# PCB.net
KiCad netlist of a schematic drawn in Altium Designer
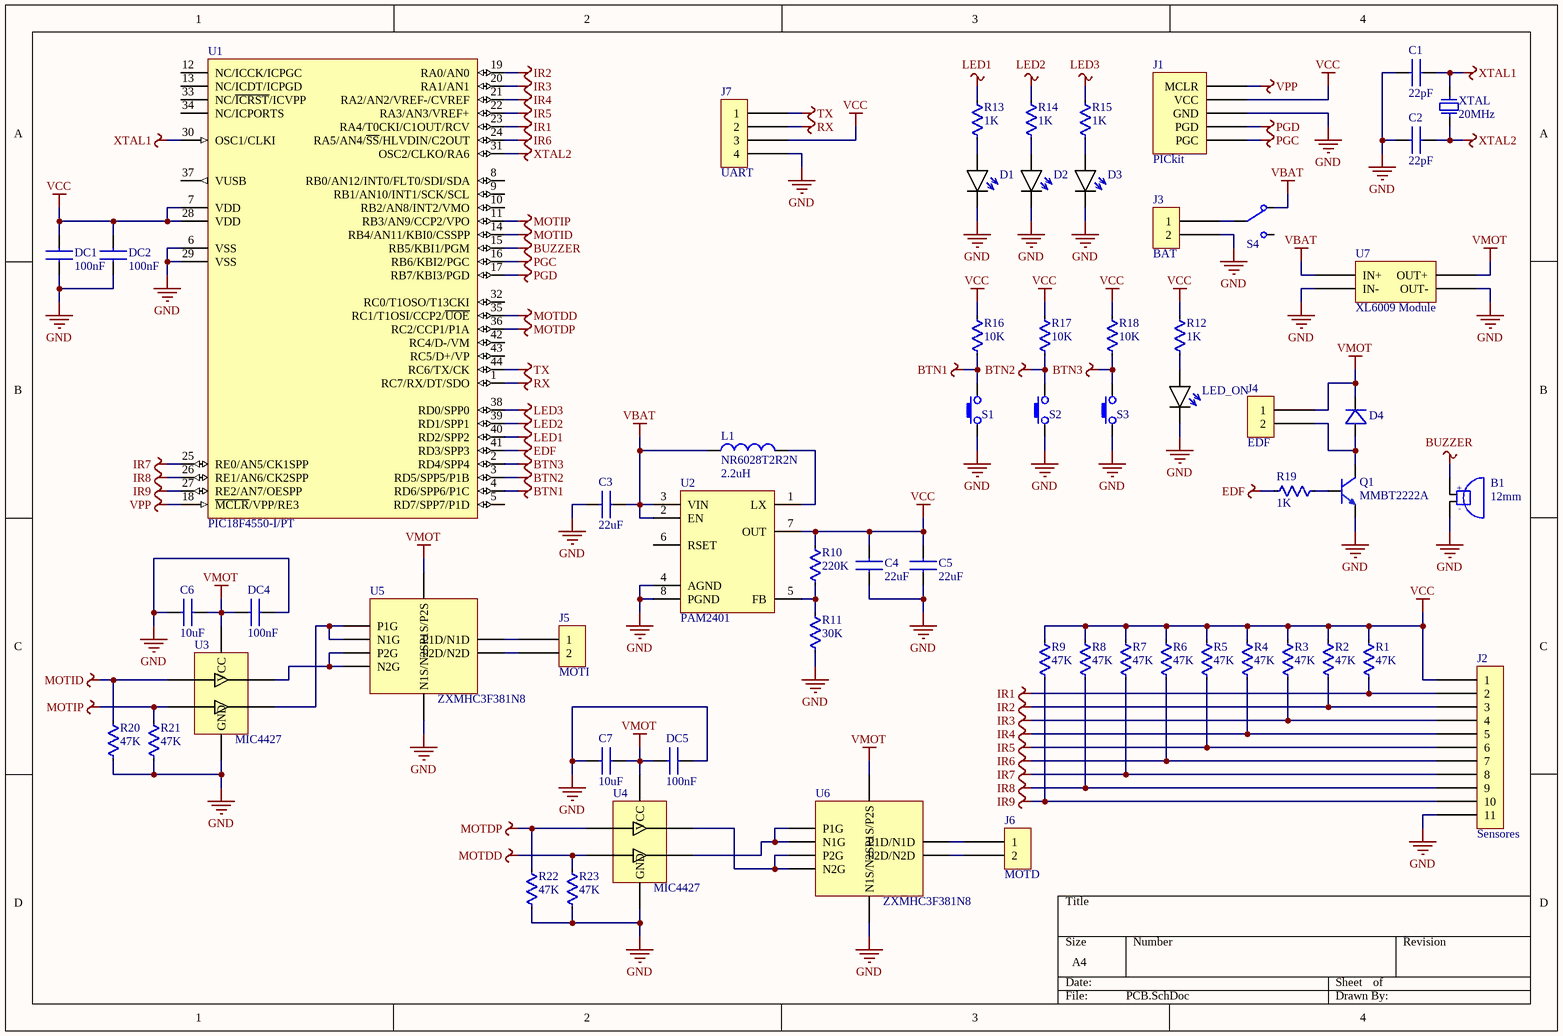
[diagram p0: PCB.SchDoc]

(export (version "E")
  (design (tool "Eeschema 10.0.6"))
  (components
    (comp (ref "B1")
      (value "12mm")
      (footprint "BUZZER-12MM")
      (libsource (lib "AltiumLibrary") (part "BUZZER-ACTIVE"))
    )
    (comp (ref "C1")
      (value "22pF")
      (footprint "C1206")
      (fields (field (name "Comment") "CAP-CER"))
      (libsource (lib "AltiumLibrary") (part "CAP-CER"))
    )
    (comp (ref "C2")
      (value "22pF")
      (footprint "C1206")
      (fields (field (name "Comment") "CAP-CER"))
      (libsource (lib "AltiumLibrary") (part "CAP-CER"))
    )
    (comp (ref "C3")
      (value "22uF")
      (footprint "C1206")
      (fields (field (name "Comment") "CAP-CER"))
      (libsource (lib "AltiumLibrary") (part "CAP-CER"))
    )
    (comp (ref "C4")
      (value "22uF")
      (footprint "C1206")
      (fields (field (name "Comment") "CAP-CER"))
      (libsource (lib "AltiumLibrary") (part "CAP-CER"))
    )
    (comp (ref "C5")
      (value "22uF")
      (footprint "C1206")
      (fields (field (name "Comment") "CAP-CER"))
      (libsource (lib "AltiumLibrary") (part "CAP-CER"))
    )
    (comp (ref "C6")
      (value "10uF")
      (footprint "C1206")
      (fields (field (name "Comment") "CAP-CER"))
      (libsource (lib "AltiumLibrary") (part "CAP-CER"))
    )
    (comp (ref "C7")
      (value "10uF")
      (footprint "C1206")
      (fields (field (name "Comment") "CAP-CER"))
      (libsource (lib "AltiumLibrary") (part "CAP-CER"))
    )
    (comp (ref "D1") (value "LED") (footprint "LED-3MM-RED") (libsource (lib "AltiumLibrary") (part "LED")))
    (comp (ref "D2")
      (value "LED")
      (footprint "LED-3MM-YELLOW")
      (libsource (lib "AltiumLibrary") (part "LED"))
    )
    (comp (ref "D3") (value "LED") (footprint "LED-3MM-GREEN") (libsource (lib "AltiumLibrary") (part "LED")))
    (comp (ref "D4") (value "1N4007") (footprint "DO-214AC") (libsource (lib "AltiumLibrary") (part "DIODE")))
    (comp (ref "DC1")
      (value "100nF")
      (footprint "C1206")
      (fields (field (name "Comment") "CAP-CER"))
      (libsource (lib "AltiumLibrary") (part "CAP-CER"))
    )
    (comp (ref "DC2")
      (value "100nF")
      (footprint "C1206")
      (fields (field (name "Comment") "CAP-CER"))
      (libsource (lib "AltiumLibrary") (part "CAP-CER"))
    )
    (comp (ref "DC4")
      (value "100nF")
      (footprint "C1206")
      (fields (field (name "Comment") "CAP-CER"))
      (libsource (lib "AltiumLibrary") (part "CAP-CER"))
    )
    (comp (ref "DC5")
      (value "100nF")
      (footprint "C1206")
      (fields (field (name "Comment") "CAP-CER"))
      (libsource (lib "AltiumLibrary") (part "CAP-CER"))
    )
    (comp (ref "J1")
      (value "PICkit")
      (footprint "Header 1x5")
      (libsource (lib "AltiumLibrary") (part "PICkit"))
    )
    (comp (ref "J2")
      (value "Sensores")
      (footprint "Header 1x11")
      (libsource (lib "AltiumLibrary") (part "Header 1x11"))
    )
    (comp (ref "J3")
      (value "BAT")
      (footprint "HEADER 1x2")
      (libsource (lib "AltiumLibrary") (part "Header 1x2"))
    )
    (comp (ref "J4")
      (value "EDF")
      (footprint "HEADER 1x2")
      (libsource (lib "AltiumLibrary") (part "Header 1x2"))
    )
    (comp (ref "J5") (value "MOTI") (footprint "HEADER 1x2") (libsource (lib "") (part "Header 1x2_1")))
    (comp (ref "J6") (value "MOTD") (footprint "HEADER 1x2") (libsource (lib "") (part "Header 1x2_1")))
    (comp (ref "J7")
      (value "UART")
      (footprint "Header 1x4")
      (libsource (lib "AltiumLibrary") (part "Header 1x4"))
    )
    (comp (ref "L1")
      (value "NR6028T2R2N")
      (footprint "NR6028")
      (fields (field (name "ALTIUM_VALUE") "2.2uH"))
      (libsource (lib "AltiumLibrary") (part "INDUCTOR"))
    )
    (comp (ref "LED_ON")
      (value "LED")
      (footprint "LED-3MM-RED")
      (libsource (lib "AltiumLibrary") (part "LED"))
    )
    (comp (ref "Q1") (value "MMBT2222A") (footprint "SOT-23") (libsource (lib "AltiumLibrary") (part "NPN")))
    (comp (ref "R1")
      (value "47K")
      (footprint "R1206")
      (fields (field (name "Comment") "RES"))
      (libsource (lib "") (part "RES_1"))
    )
    (comp (ref "R2")
      (value "47K")
      (footprint "R1206")
      (fields (field (name "Comment") "RES"))
      (libsource (lib "") (part "RES_1"))
    )
    (comp (ref "R3")
      (value "47K")
      (footprint "R1206")
      (fields (field (name "Comment") "RES"))
      (libsource (lib "") (part "RES_1"))
    )
    (comp (ref "R4")
      (value "47K")
      (footprint "R1206")
      (fields (field (name "Comment") "RES"))
      (libsource (lib "") (part "RES_1"))
    )
    (comp (ref "R5")
      (value "47K")
      (footprint "R1206")
      (fields (field (name "Comment") "RES"))
      (libsource (lib "") (part "RES_1"))
    )
    (comp (ref "R6")
      (value "47K")
      (footprint "R1206")
      (fields (field (name "Comment") "RES"))
      (libsource (lib "") (part "RES_1"))
    )
    (comp (ref "R7")
      (value "47K")
      (footprint "R1206")
      (fields (field (name "Comment") "RES"))
      (libsource (lib "") (part "RES_1"))
    )
    (comp (ref "R8")
      (value "47K")
      (footprint "R1206")
      (fields (field (name "Comment") "RES"))
      (libsource (lib "") (part "RES_1"))
    )
    (comp (ref "R9")
      (value "47K")
      (footprint "R1206")
      (fields (field (name "Comment") "RES"))
      (libsource (lib "") (part "RES_1"))
    )
    (comp (ref "R10")
      (value "220K")
      (footprint "R1206")
      (fields (field (name "Comment") "RES"))
      (libsource (lib "") (part "RES_1"))
    )
    (comp (ref "R11")
      (value "30K")
      (footprint "R1206")
      (fields (field (name "Comment") "RES"))
      (libsource (lib "") (part "RES_1"))
    )
    (comp (ref "R12")
      (value "1K")
      (footprint "R1206")
      (fields (field (name "Comment") "RES"))
      (libsource (lib "") (part "RES_1"))
    )
    (comp (ref "R13")
      (value "1K")
      (footprint "R1206")
      (fields (field (name "Comment") "RES"))
      (libsource (lib "") (part "RES_1"))
    )
    (comp (ref "R14")
      (value "1K")
      (footprint "R1206")
      (fields (field (name "Comment") "RES"))
      (libsource (lib "") (part "RES_1"))
    )
    (comp (ref "R15")
      (value "1K")
      (footprint "R1206")
      (fields (field (name "Comment") "RES"))
      (libsource (lib "") (part "RES_1"))
    )
    (comp (ref "R16")
      (value "10K")
      (footprint "R1206")
      (fields (field (name "Comment") "RES"))
      (libsource (lib "") (part "RES_1"))
    )
    (comp (ref "R17")
      (value "10K")
      (footprint "R1206")
      (fields (field (name "Comment") "RES"))
      (libsource (lib "") (part "RES_1"))
    )
    (comp (ref "R18")
      (value "10K")
      (footprint "R1206")
      (fields (field (name "Comment") "RES"))
      (libsource (lib "") (part "RES_1"))
    )
    (comp (ref "R19")
      (value "1K")
      (footprint "R1206")
      (fields (field (name "Comment") "RES"))
      (libsource (lib "AltiumLibrary") (part "RES"))
    )
    (comp (ref "R20")
      (value "47K")
      (footprint "R1206")
      (fields (field (name "Comment") "RES"))
      (libsource (lib "") (part "RES_1"))
    )
    (comp (ref "R21")
      (value "47K")
      (footprint "R1206")
      (fields (field (name "Comment") "RES"))
      (libsource (lib "") (part "RES_1"))
    )
    (comp (ref "R22")
      (value "47K")
      (footprint "R1206")
      (fields (field (name "Comment") "RES"))
      (libsource (lib "") (part "RES_1"))
    )
    (comp (ref "R23")
      (value "47K")
      (footprint "R1206")
      (fields (field (name "Comment") "RES"))
      (libsource (lib "") (part "RES_1"))
    )
    (comp (ref "S1")
      (value "BUTTON")
      (footprint "TACT_SWITCH-SMALL-4PIN")
      (libsource (lib "AltiumLibrary") (part "BUTTON"))
    )
    (comp (ref "S2")
      (value "BUTTON")
      (footprint "TACT_SWITCH-SMALL-4PIN")
      (libsource (lib "AltiumLibrary") (part "BUTTON"))
    )
    (comp (ref "S3")
      (value "BUTTON")
      (footprint "TACT_SWITCH-SMALL-4PIN")
      (libsource (lib "AltiumLibrary") (part "BUTTON"))
    )
    (comp (ref "S4")
      (value "SLIDE-SWITCH")
      (footprint "SWITCH")
      (libsource (lib "AltiumLibrary") (part "SLIDE-SWITCH"))
    )
    (comp (ref "U1")
      (value "PIC18F4550-I/PT")
      (footprint "TQFP-PT44_L")
      (fields (field (name "PUBLISHER") "Altium Limited"))
      (libsource (lib "AltiumLibrary") (part "PIC18F4550-I/PT"))
    )
    (comp (ref "U2")
      (value "PAM2401")
      (footprint "MSOP-8")
      (libsource (lib "AltiumLibrary") (part "PAM2401"))
    )
    (comp (ref "U3") (value "MIC4427") (footprint "SOIC-8") (libsource (lib "AltiumLibrary") (part "4427")))
    (comp (ref "U4") (value "MIC4427") (footprint "SOIC-8") (libsource (lib "AltiumLibrary") (part "4427")))
    (comp (ref "U5")
      (value "ZXMHC3F381N8")
      (footprint "SOIC-8")
      (libsource (lib "AltiumLibrary") (part "ZXMHC3F381N8"))
    )
    (comp (ref "U6")
      (value "ZXMHC3F381N8")
      (footprint "SOIC-8")
      (libsource (lib "AltiumLibrary") (part "ZXMHC3F381N8"))
    )
    (comp (ref "U7")
      (value "XL6009 Module")
      (footprint "XL6009 mdl")
      (libsource (lib "AltiumLibrary") (part "XL6009 Module"))
    )
    (comp (ref "XTAL")
      (value "XTAL")
      (footprint "HC-49/S")
      (fields (field (name "FREQUENCY") "20MHz"))
      (libsource (lib "AltiumLibrary") (part "XTAL"))
    )
  )
  (nets
    (net (code "1") (name "BTN1") (class "Default")
      (node (ref "R16") (pin "1") (pintype "passive"))
      (node (ref "S1") (pin "2") (pintype "passive"))
      (node (ref "U1") (pin "4") (pinfunction "RD6/SPP6/P1C_4") (pintype "bidirectional"))
    )
    (net (code "2") (name "BTN2") (class "Default")
      (node (ref "R17") (pin "1") (pintype "passive"))
      (node (ref "S2") (pin "2") (pintype "passive"))
      (node (ref "U1") (pin "3") (pinfunction "RD5/SPP5/P1B_3") (pintype "bidirectional"))
    )
    (net (code "3") (name "BTN3") (class "Default")
      (node (ref "R18") (pin "1") (pintype "passive"))
      (node (ref "S3") (pin "2") (pintype "passive"))
      (node (ref "U1") (pin "2") (pinfunction "RD4/SPP4_2") (pintype "bidirectional"))
    )
    (net (code "4") (name "BUZZER") (class "Default")
      (node (ref "B1") (pin "1") (pinfunction "+_1") (pintype "passive"))
      (node (ref "U1") (pin "15") (pinfunction "RB5/KBI1/PGM_15") (pintype "bidirectional"))
    )
    (net (code "5") (name "EDF") (class "Default")
      (node (ref "R19") (pin "1") (pintype "passive"))
      (node (ref "U1") (pin "41") (pinfunction "RD3/SPP3_41") (pintype "bidirectional"))
    )
    (net (code "6") (name "GND") (class "Default")
      (node (ref "B1") (pin "2") (pinfunction "-_2") (pintype "passive"))
      (node (ref "C1") (pin "1") (pintype "passive"))
      (node (ref "C2") (pin "1") (pintype "passive"))
      (node (ref "C3") (pin "1") (pintype "passive"))
      (node (ref "C4") (pin "1") (pintype "passive"))
      (node (ref "C5") (pin "1") (pintype "passive"))
      (node (ref "C6") (pin "2") (pintype "passive"))
      (node (ref "C7") (pin "2") (pintype "passive"))
      (node (ref "D1") (pin "K") (pintype "passive"))
      (node (ref "D2") (pin "K") (pintype "passive"))
      (node (ref "D3") (pin "K") (pintype "passive"))
      (node (ref "DC1") (pin "1") (pintype "passive"))
      (node (ref "DC2") (pin "1") (pintype "passive"))
      (node (ref "DC4") (pin "2") (pintype "passive"))
      (node (ref "DC5") (pin "2") (pintype "passive"))
      (node (ref "J1") (pin "3") (pinfunction "GND_3") (pintype "power_in"))
      (node (ref "J2") (pin "11") (pinfunction "11_11") (pintype "passive"))
      (node (ref "J3") (pin "2") (pinfunction "2_2") (pintype "passive"))
      (node (ref "J7") (pin "4") (pinfunction "4_4") (pintype "passive"))
      (node (ref "LED_ON") (pin "K") (pintype "passive"))
      (node (ref "Q1") (pin "E") (pinfunction "E_E") (pintype "passive"))
      (node (ref "R11") (pin "1") (pintype "passive"))
      (node (ref "R20") (pin "1") (pintype "passive"))
      (node (ref "R21") (pin "1") (pintype "passive"))
      (node (ref "R22") (pin "1") (pintype "passive"))
      (node (ref "R23") (pin "1") (pintype "passive"))
      (node (ref "S1") (pin "1") (pintype "passive"))
      (node (ref "S2") (pin "1") (pintype "passive"))
      (node (ref "S3") (pin "1") (pintype "passive"))
      (node (ref "U1") (pin "29") (pinfunction "VSS_29") (pintype "power_in"))
      (node (ref "U1") (pin "6") (pinfunction "VSS_6") (pintype "power_in"))
      (node (ref "U2") (pin "4") (pinfunction "AGND_4") (pintype "passive"))
      (node (ref "U2") (pin "8") (pinfunction "PGND_8") (pintype "passive"))
      (node (ref "U3") (pin "3") (pinfunction "GND_3") (pintype "passive"))
      (node (ref "U4") (pin "3") (pinfunction "GND_3") (pintype "passive"))
      (node (ref "U5") (pin "3") (pinfunction "N1S/N2S_3") (pintype "passive"))
      (node (ref "U6") (pin "3") (pinfunction "N1S/N2S_3") (pintype "passive"))
      (node (ref "U7") (pin "1") (pinfunction "IN-_1") (pintype "passive"))
      (node (ref "U7") (pin "2") (pinfunction "OUT-_2") (pintype "passive"))
    )
    (net (code "7") (name "IR1") (class "Default")
      (node (ref "J2") (pin "2") (pinfunction "2_2") (pintype "passive"))
      (node (ref "R1") (pin "1") (pintype "passive"))
      (node (ref "U1") (pin "23") (pinfunction "RA4/T0CKI/C1OUT/RCV_23") (pintype "bidirectional"))
    )
    (net (code "8") (name "IR2") (class "Default")
      (node (ref "J2") (pin "3") (pinfunction "3_3") (pintype "passive"))
      (node (ref "R2") (pin "1") (pintype "passive"))
      (node (ref "U1") (pin "19") (pinfunction "RA0/AN0_19") (pintype "bidirectional"))
    )
    (net (code "9") (name "IR3") (class "Default")
      (node (ref "J2") (pin "4") (pinfunction "4_4") (pintype "passive"))
      (node (ref "R3") (pin "1") (pintype "passive"))
      (node (ref "U1") (pin "20") (pinfunction "RA1/AN1_20") (pintype "bidirectional"))
    )
    (net (code "10") (name "IR4") (class "Default")
      (node (ref "J2") (pin "5") (pinfunction "5_5") (pintype "passive"))
      (node (ref "R4") (pin "1") (pintype "passive"))
      (node (ref "U1") (pin "21") (pinfunction "RA2/AN2/VREF-/CVREF_21") (pintype "bidirectional"))
    )
    (net (code "11") (name "IR5") (class "Default")
      (node (ref "J2") (pin "6") (pinfunction "6_6") (pintype "passive"))
      (node (ref "R5") (pin "1") (pintype "passive"))
      (node (ref "U1") (pin "22") (pinfunction "RA3/AN3/VREF+_22") (pintype "bidirectional"))
    )
    (net (code "12") (name "IR6") (class "Default")
      (node (ref "J2") (pin "7") (pinfunction "7_7") (pintype "passive"))
      (node (ref "R6") (pin "1") (pintype "passive"))
      (node (ref "U1") (pin "24") (pinfunction "RA5/AN4/~{SS}/HLVDIN/C2OUT_24") (pintype "bidirectional"))
    )
    (net (code "13") (name "IR7") (class "Default")
      (node (ref "J2") (pin "8") (pinfunction "8_8") (pintype "passive"))
      (node (ref "R7") (pin "1") (pintype "passive"))
      (node (ref "U1") (pin "25") (pinfunction "RE0/AN5/CK1SPP_25") (pintype "bidirectional"))
    )
    (net (code "14") (name "IR8") (class "Default")
      (node (ref "J2") (pin "9") (pinfunction "9_9") (pintype "passive"))
      (node (ref "R8") (pin "1") (pintype "passive"))
      (node (ref "U1") (pin "26") (pinfunction "RE1/AN6/CK2SPP_26") (pintype "bidirectional"))
    )
    (net (code "15") (name "IR9") (class "Default")
      (node (ref "J2") (pin "10") (pinfunction "10_10") (pintype "passive"))
      (node (ref "R9") (pin "1") (pintype "passive"))
      (node (ref "U1") (pin "27") (pinfunction "RE2/AN7/OESPP_27") (pintype "bidirectional"))
    )
    (net (code "16") (name "LED1") (class "Default")
      (node (ref "R13") (pin "2") (pintype "passive"))
      (node (ref "U1") (pin "40") (pinfunction "RD2/SPP2_40") (pintype "bidirectional"))
    )
    (net (code "17") (name "LED2") (class "Default")
      (node (ref "R14") (pin "2") (pintype "passive"))
      (node (ref "U1") (pin "39") (pinfunction "RD1/SPP1_39") (pintype "bidirectional"))
    )
    (net (code "18") (name "LED3") (class "Default")
      (node (ref "R15") (pin "2") (pintype "passive"))
      (node (ref "U1") (pin "38") (pinfunction "RD0/SPP0_38") (pintype "bidirectional"))
    )
    (net (code "19") (name "MOTDD") (class "Default")
      (node (ref "R23") (pin "2") (pintype "passive"))
      (node (ref "U1") (pin "35") (pinfunction "RC1/T1OSI/CCP2/~{UOE}_35") (pintype "bidirectional"))
      (node (ref "U4") (pin "4") (pinfunction "INB_4") (pintype "passive"))
    )
    (net (code "20") (name "MOTDP") (class "Default")
      (node (ref "R22") (pin "2") (pintype "passive"))
      (node (ref "U1") (pin "36") (pinfunction "RC2/CCP1/P1A_36") (pintype "bidirectional"))
      (node (ref "U4") (pin "2") (pinfunction "INA_2") (pintype "passive"))
    )
    (net (code "21") (name "MOTID") (class "Default")
      (node (ref "R20") (pin "2") (pintype "passive"))
      (node (ref "U1") (pin "14") (pinfunction "RB4/AN11/KBI0/CSSPP_14") (pintype "bidirectional"))
      (node (ref "U3") (pin "2") (pinfunction "INA_2") (pintype "passive"))
    )
    (net (code "22") (name "MOTIP") (class "Default")
      (node (ref "R21") (pin "2") (pintype "passive"))
      (node (ref "U1") (pin "11") (pinfunction "RB3/AN9/CCP2/VPO_11") (pintype "bidirectional"))
      (node (ref "U3") (pin "4") (pinfunction "INB_4") (pintype "passive"))
    )
    (net (code "23") (name "Net-(D1-PadA)") (class "Default")
      (node (ref "D1") (pin "A") (pintype "passive"))
      (node (ref "R13") (pin "1") (pintype "passive"))
    )
    (net (code "24") (name "Net-(D2-PadA)") (class "Default")
      (node (ref "D2") (pin "A") (pintype "passive"))
      (node (ref "R14") (pin "1") (pintype "passive"))
    )
    (net (code "25") (name "Net-(D3-PadA)") (class "Default")
      (node (ref "D3") (pin "A") (pintype "passive"))
      (node (ref "R15") (pin "1") (pintype "passive"))
    )
    (net (code "26") (name "Net-(D4-PadA)") (class "Default")
      (node (ref "D4") (pin "A") (pintype "passive"))
      (node (ref "J4") (pin "2") (pinfunction "2_2") (pintype "passive"))
      (node (ref "Q1") (pin "C") (pinfunction "C_C") (pintype "passive"))
    )
    (net (code "27") (name "Net-(J3-Pad1)") (class "Default")
      (node (ref "J3") (pin "1") (pinfunction "1_1") (pintype "passive"))
      (node (ref "S4") (pin "2") (pintype "power_in"))
    )
    (net (code "28") (name "Net-(LED_ON-PadA)") (class "Default")
      (node (ref "LED_ON") (pin "A") (pintype "passive"))
      (node (ref "R12") (pin "1") (pintype "passive"))
    )
    (net (code "29") (name "Net-(Q1-PadB)") (class "Default")
      (node (ref "Q1") (pin "B") (pinfunction "B_B") (pintype "passive"))
      (node (ref "R19") (pin "2") (pintype "passive"))
    )
    (net (code "30") (name "Net-(U2-FB)") (class "Default")
      (node (ref "R10") (pin "1") (pintype "passive"))
      (node (ref "R11") (pin "2") (pintype "passive"))
      (node (ref "U2") (pin "5") (pinfunction "FB_5") (pintype "passive"))
    )
    (net (code "31") (name "Net-(U2-LX)") (class "Default")
      (node (ref "L1") (pin "2") (pinfunction "2_2") (pintype "passive"))
      (node (ref "U2") (pin "1") (pinfunction "LX_1") (pintype "passive"))
    )
    (net (code "32") (name "Net-(U3-OUTA)") (class "Default")
      (node (ref "U3") (pin "7") (pinfunction "OUTA_7") (pintype "passive"))
      (node (ref "U5") (pin "4") (pinfunction "N2G_4") (pintype "passive"))
      (node (ref "U5") (pin "5") (pinfunction "P2G_5") (pintype "passive"))
    )
    (net (code "33") (name "Net-(U3-OUTB)") (class "Default")
      (node (ref "U3") (pin "5") (pinfunction "OUTB_5") (pintype "passive"))
      (node (ref "U5") (pin "1") (pinfunction "N1G_1") (pintype "passive"))
      (node (ref "U5") (pin "8") (pinfunction "P1G_8") (pintype "passive"))
    )
    (net (code "34") (name "Net-(U4-OUTA)") (class "Default")
      (node (ref "U4") (pin "7") (pinfunction "OUTA_7") (pintype "passive"))
      (node (ref "U6") (pin "4") (pinfunction "N2G_4") (pintype "passive"))
      (node (ref "U6") (pin "5") (pinfunction "P2G_5") (pintype "passive"))
    )
    (net (code "35") (name "Net-(U4-OUTB)") (class "Default")
      (node (ref "U4") (pin "5") (pinfunction "OUTB_5") (pintype "passive"))
      (node (ref "U6") (pin "1") (pinfunction "N1G_1") (pintype "passive"))
      (node (ref "U6") (pin "8") (pinfunction "P1G_8") (pintype "passive"))
    )
    (net (code "36") (name "Net-(U5-P1D{slash}N1D)") (class "Default")
      (node (ref "J5") (pin "1") (pinfunction "1_1") (pintype "passive"))
      (node (ref "U5") (pin "2") (pinfunction "P1D/N1D_2") (pintype "passive"))
    )
    (net (code "37") (name "Net-(U5-P2D{slash}N2D)") (class "Default")
      (node (ref "J5") (pin "2") (pinfunction "2_2") (pintype "passive"))
      (node (ref "U5") (pin "6") (pinfunction "P2D/N2D_6") (pintype "passive"))
    )
    (net (code "38") (name "Net-(U6-P1D{slash}N1D)") (class "Default")
      (node (ref "J6") (pin "1") (pinfunction "1_1") (pintype "passive"))
      (node (ref "U6") (pin "2") (pinfunction "P1D/N1D_2") (pintype "passive"))
    )
    (net (code "39") (name "Net-(U6-P2D{slash}N2D)") (class "Default")
      (node (ref "J6") (pin "2") (pinfunction "2_2") (pintype "passive"))
      (node (ref "U6") (pin "6") (pinfunction "P2D/N2D_6") (pintype "passive"))
    )
    (net (code "40") (name "PGC") (class "Default")
      (node (ref "J1") (pin "5") (pinfunction "PGC_5") (pintype "passive"))
      (node (ref "U1") (pin "16") (pinfunction "RB6/KBI2/PGC_16") (pintype "bidirectional"))
    )
    (net (code "41") (name "PGD") (class "Default")
      (node (ref "J1") (pin "4") (pinfunction "PGD_4") (pintype "passive"))
      (node (ref "U1") (pin "17") (pinfunction "RB7/KBI3/PGD_17") (pintype "bidirectional"))
    )
    (net (code "42") (name "RX") (class "Default")
      (node (ref "J7") (pin "2") (pinfunction "2_2") (pintype "passive"))
      (node (ref "U1") (pin "1") (pinfunction "RC7/RX/DT/SDO_1") (pintype "bidirectional"))
    )
    (net (code "43") (name "TX") (class "Default")
      (node (ref "J7") (pin "1") (pinfunction "1_1") (pintype "passive"))
      (node (ref "U1") (pin "44") (pinfunction "RC6/TX/CK_44") (pintype "bidirectional"))
    )
    (net (code "44") (name "VBAT") (class "Default")
      (node (ref "C3") (pin "2") (pintype "passive"))
      (node (ref "L1") (pin "1") (pinfunction "1_1") (pintype "passive"))
      (node (ref "S4") (pin "1") (pintype "power_in"))
      (node (ref "U2") (pin "2") (pinfunction "EN_2") (pintype "passive"))
      (node (ref "U2") (pin "3") (pinfunction "VIN_3") (pintype "passive"))
      (node (ref "U7") (pin "0") (pinfunction "IN+_0") (pintype "passive"))
    )
    (net (code "45") (name "VCC") (class "Default")
      (node (ref "C4") (pin "2") (pintype "passive"))
      (node (ref "C5") (pin "2") (pintype "passive"))
      (node (ref "DC1") (pin "2") (pintype "passive"))
      (node (ref "DC2") (pin "2") (pintype "passive"))
      (node (ref "J1") (pin "2") (pinfunction "VCC_2") (pintype "power_in"))
      (node (ref "J2") (pin "1") (pinfunction "1_1") (pintype "passive"))
      (node (ref "J7") (pin "3") (pinfunction "3_3") (pintype "passive"))
      (node (ref "R1") (pin "2") (pintype "passive"))
      (node (ref "R10") (pin "2") (pintype "passive"))
      (node (ref "R12") (pin "2") (pintype "passive"))
      (node (ref "R16") (pin "2") (pintype "passive"))
      (node (ref "R17") (pin "2") (pintype "passive"))
      (node (ref "R18") (pin "2") (pintype "passive"))
      (node (ref "R2") (pin "2") (pintype "passive"))
      (node (ref "R3") (pin "2") (pintype "passive"))
      (node (ref "R4") (pin "2") (pintype "passive"))
      (node (ref "R5") (pin "2") (pintype "passive"))
      (node (ref "R6") (pin "2") (pintype "passive"))
      (node (ref "R7") (pin "2") (pintype "passive"))
      (node (ref "R8") (pin "2") (pintype "passive"))
      (node (ref "R9") (pin "2") (pintype "passive"))
      (node (ref "U1") (pin "28") (pinfunction "VDD_28") (pintype "power_in"))
      (node (ref "U1") (pin "7") (pinfunction "VDD_7") (pintype "power_in"))
      (node (ref "U2") (pin "7") (pinfunction "OUT_7") (pintype "passive"))
    )
    (net (code "46") (name "VMOT") (class "Default")
      (node (ref "C6") (pin "1") (pintype "passive"))
      (node (ref "C7") (pin "1") (pintype "passive"))
      (node (ref "D4") (pin "K") (pintype "passive"))
      (node (ref "DC4") (pin "1") (pintype "passive"))
      (node (ref "DC5") (pin "1") (pintype "passive"))
      (node (ref "J4") (pin "1") (pinfunction "1_1") (pintype "passive"))
      (node (ref "U3") (pin "6") (pinfunction "VCC_6") (pintype "passive"))
      (node (ref "U4") (pin "6") (pinfunction "VCC_6") (pintype "passive"))
      (node (ref "U5") (pin "7") (pinfunction "P1S/P2S_7") (pintype "passive"))
      (node (ref "U6") (pin "7") (pinfunction "P1S/P2S_7") (pintype "passive"))
      (node (ref "U7") (pin "3") (pinfunction "OUT+_3") (pintype "passive"))
    )
    (net (code "47") (name "VPP") (class "Default")
      (node (ref "J1") (pin "1") (pinfunction "MCLR_1") (pintype "passive"))
      (node (ref "U1") (pin "18") (pinfunction "~{MCLR}/VPP/RE3_18") (pintype "input"))
    )
    (net (code "48") (name "XTAL1") (class "Default")
      (node (ref "C1") (pin "2") (pintype "passive"))
      (node (ref "U1") (pin "30") (pinfunction "OSC1/CLKI_30") (pintype "input"))
      (node (ref "XTAL") (pin "2") (pintype "passive"))
    )
    (net (code "49") (name "XTAL2") (class "Default")
      (node (ref "C2") (pin "2") (pintype "passive"))
      (node (ref "U1") (pin "31") (pinfunction "OSC2/CLKO/RA6_31") (pintype "bidirectional"))
      (node (ref "XTAL") (pin "1") (pintype "passive"))
    )
    (net (code "50") (name "unconnected-(S4-Pad3)") (class "Default")
      (node (ref "S4") (pin "3") (pintype "power_in"))
    )
    (net (code "51") (name "unconnected-(U1-NC{slash}ICCK{slash}ICPGC-Pad12)") (class "Default")
      (node (ref "U1") (pin "12") (pinfunction "NC/ICCK/ICPGC_12") (pintype "passive"))
    )
    (net (code "52") (name "unconnected-(U1-NC{slash}ICDT{slash}ICPGD-Pad13)") (class "Default")
      (node (ref "U1") (pin "13") (pinfunction "NC/ICDT/ICPGD_13") (pintype "passive"))
    )
    (net (code "53") (name "unconnected-(U1-NC{slash}ICPORTS-Pad34)") (class "Default")
      (node (ref "U1") (pin "34") (pinfunction "NC/ICPORTS_34") (pintype "passive"))
    )
    (net (code "54") (name "unconnected-(U1-NC{slash}~{ICRST}{slash}ICVPP-Pad33)") (class "Default")
      (node (ref "U1") (pin "33") (pinfunction "NC/~{ICRST}/ICVPP_33") (pintype "passive"))
    )
    (net (code "55") (name "unconnected-(U1-RB0{slash}AN12{slash}INT0{slash}FLT0{slash}SDI{slash}SDA-Pad8)") (class "Default")
      (node (ref "U1") (pin "8") (pinfunction "RB0/AN12/INT0/FLT0/SDI/SDA_8") (pintype "bidirectional"))
    )
    (net (code "56") (name "unconnected-(U1-RB1{slash}AN10{slash}INT1{slash}SCK{slash}SCL-Pad9)") (class "Default")
      (node (ref "U1") (pin "9") (pinfunction "RB1/AN10/INT1/SCK/SCL_9") (pintype "bidirectional"))
    )
    (net (code "57") (name "unconnected-(U1-RB2{slash}AN8{slash}INT2{slash}VMO-Pad10)") (class "Default")
      (node (ref "U1") (pin "10") (pinfunction "RB2/AN8/INT2/VMO_10") (pintype "bidirectional"))
    )
    (net (code "58") (name "unconnected-(U1-RC0{slash}T1OSO{slash}T13CKI-Pad32)") (class "Default")
      (node (ref "U1") (pin "32") (pinfunction "RC0/T1OSO/T13CKI_32") (pintype "bidirectional"))
    )
    (net (code "59") (name "unconnected-(U1-RC4{slash}D-{slash}VM-Pad42)") (class "Default")
      (node (ref "U1") (pin "42") (pinfunction "RC4/D-/VM_42") (pintype "bidirectional"))
    )
    (net (code "60") (name "unconnected-(U1-RC5{slash}D+{slash}VP-Pad43)") (class "Default")
      (node (ref "U1") (pin "43") (pinfunction "RC5/D+/VP_43") (pintype "bidirectional"))
    )
    (net (code "61") (name "unconnected-(U1-RD7{slash}SPP7{slash}P1D-Pad5)") (class "Default")
      (node (ref "U1") (pin "5") (pinfunction "RD7/SPP7/P1D_5") (pintype "bidirectional"))
    )
    (net (code "62") (name "unconnected-(U1-VUSB-Pad37)") (class "Default")
      (node (ref "U1") (pin "37") (pinfunction "VUSB_37") (pintype "output"))
    )
    (net (code "63") (name "unconnected-(U2-RSET-Pad6)") (class "Default")
      (node (ref "U2") (pin "6") (pinfunction "RSET_6") (pintype "passive"))
    )
  )
)
